# Sensor_PCB_M3.net
KiCad netlist of a schematic drawn in EAGLE
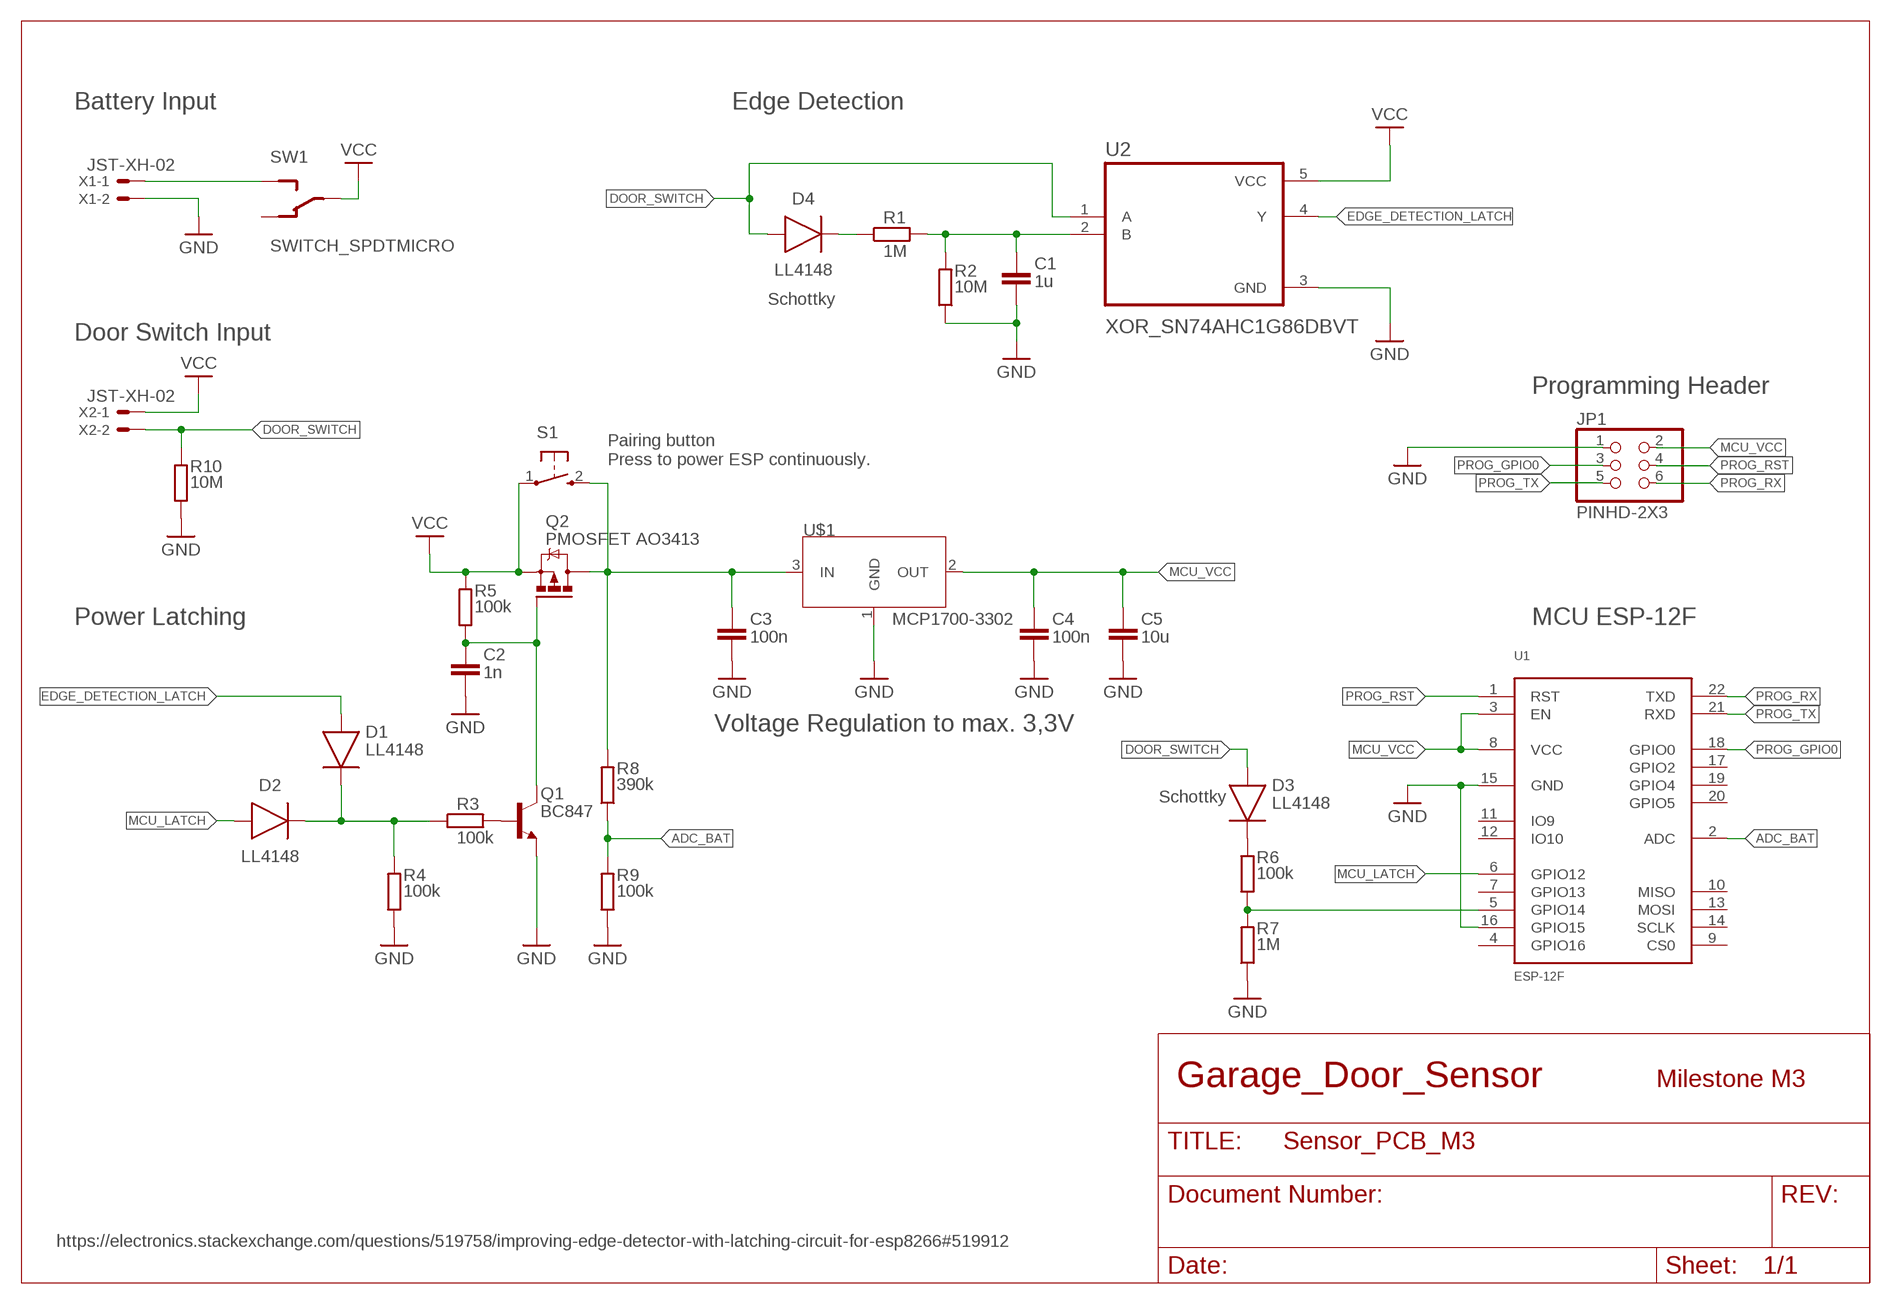
[diagram p0: schematic, sheet 1]

(export (version "E")
  (design (tool "Eeschema 10.0.6"))
  (components
    (comp (ref "C1")
      (value "1u")
      (footprint "eagle-import:CAPC2012X110")
      (libsource (lib "eagle-import") (part "CCHIP-0805(2012-METRIC)_"))
    )
    (comp (ref "C2")
      (value "1n")
      (footprint "eagle-import:CAPC2012X110")
      (libsource (lib "eagle-import") (part "CCHIP-0805(2012-METRIC)_"))
    )
    (comp (ref "C3")
      (value "100n")
      (footprint "eagle-import:CAPC2012X110")
      (libsource (lib "eagle-import") (part "CCHIP-0805(2012-METRIC)_"))
    )
    (comp (ref "C4")
      (value "100n")
      (footprint "eagle-import:CAPC2012X110")
      (libsource (lib "eagle-import") (part "CCHIP-0805(2012-METRIC)_"))
    )
    (comp (ref "C5")
      (value "10u")
      (footprint "eagle-import:CAPC2012X110")
      (libsource (lib "eagle-import") (part "CCHIP-0805(2012-METRIC)_"))
    )
    (comp (ref "D1")
      (value "LL4148")
      (footprint "eagle-import:DIOMELF3516")
      (fields (field (name "MANUFACTURER") "ON Semiconductor "))
      (libsource (lib "eagle-import") (part "DIODE__SOD-80LL4148"))
    )
    (comp (ref "D2")
      (value "LL4148")
      (footprint "eagle-import:DIOMELF3516")
      (fields (field (name "MANUFACTURER") "ON Semiconductor "))
      (libsource (lib "eagle-import") (part "DIODE__SOD-80LL4148"))
    )
    (comp (ref "D3")
      (value "LL4148")
      (footprint "eagle-import:DIOMELF3516")
      (fields (field (name "MANUFACTURER") "ON Semiconductor "))
      (libsource (lib "eagle-import") (part "DIODE__SOD-80LL4148"))
    )
    (comp (ref "D4")
      (value "LL4148")
      (footprint "eagle-import:DIOMELF3516")
      (fields (field (name "MANUFACTURER") "ON Semiconductor "))
      (libsource (lib "eagle-import") (part "DIODE__SOD-80LL4148"))
    )
    (comp (ref "JP1")
      (value "PINHD-2X3")
      (footprint "eagle-import:2X03")
      (fields (field (name "MANUFACTURER") "Generic"))
      (libsource (lib "eagle-import") (part "PINHD-2X3"))
    )
    (comp (ref "Q1")
      (value "BC847")
      (footprint "eagle-import:SOT95P237X112-3N")
      (libsource (lib "eagle-import") (part "NPNSOT23-BEC_"))
    )
    (comp (ref "Q2")
      (value "PMOSFET AO3413")
      (footprint "eagle-import:SOT23")
      (libsource (lib "eagle-import") (part "PMOSFETSOT23-GSD_"))
    )
    (comp (ref "R1")
      (value "1M")
      (footprint "eagle-import:R0805")
      (libsource (lib "eagle-import") (part "R-EU_R0805"))
    )
    (comp (ref "R2")
      (value "10M")
      (footprint "eagle-import:R0805")
      (libsource (lib "eagle-import") (part "R-EU_R0805"))
    )
    (comp (ref "R3")
      (value "100k")
      (footprint "eagle-import:R0805")
      (libsource (lib "eagle-import") (part "R-EU_R0805"))
    )
    (comp (ref "R4")
      (value "100k")
      (footprint "eagle-import:R0805")
      (libsource (lib "eagle-import") (part "R-EU_R0805"))
    )
    (comp (ref "R5")
      (value "100k")
      (footprint "eagle-import:R0805")
      (libsource (lib "eagle-import") (part "R-EU_R0805"))
    )
    (comp (ref "R6")
      (value "100k")
      (footprint "eagle-import:R0805")
      (libsource (lib "eagle-import") (part "R-EU_R0805"))
    )
    (comp (ref "R7")
      (value "1M")
      (footprint "eagle-import:R0805")
      (libsource (lib "eagle-import") (part "R-EU_R0805"))
    )
    (comp (ref "R8")
      (value "390k")
      (footprint "eagle-import:R0805")
      (libsource (lib "eagle-import") (part "R-EU_R0805"))
    )
    (comp (ref "R9")
      (value "100k")
      (footprint "eagle-import:R0805")
      (libsource (lib "eagle-import") (part "R-EU_R0805"))
    )
    (comp (ref "R10")
      (value "10M")
      (footprint "eagle-import:R0805")
      (libsource (lib "eagle-import") (part "R-EU_R0805"))
    )
    (comp (ref "S1")
      (value "KURZHUBTASTER")
      (footprint "eagle-import:B3F-10XX")
      (libsource (lib "eagle-import") (part "KURZHUBTASTER"))
    )
    (comp (ref "SW1")
      (value "SWITCH_SPDTMICRO")
      (footprint "eagle-import:MICROSWITCH_SPDT")
      (libsource (lib "eagle-import") (part "SWITCH_SPDTMICRO"))
    )
    (comp (ref "U$1")
      (value "MCP1700-3302")
      (footprint "eagle-import:SOT23")
      (libsource (lib "eagle-import") (part "MCP1700-3302"))
    )
    (comp (ref "U1")
      (value "ESP-12F")
      (footprint "eagle-import:ESP-12F")
      (fields (field (name "MF") "AI-Thinker"))
      (libsource (lib "eagle-import") (part "ESP-12F"))
    )
    (comp (ref "U2")
      (value "XOR_SN74AHC1G86DBVT")
      (footprint "eagle-import:SOT95P280X145-5N")
      (fields (field (name "MF") "Texas Instruments") (field (name "MP") "SN74AHC1G86DBVT"))
      (libsource (lib "eagle-import") (part "SN74AHC1G86DBVT"))
    )
    (comp (ref "X1")
      (value "JST-XH-02")
      (footprint "eagle-import:JST-XH-02-PACKAGE-LONG-PAD")
      (libsource (lib "eagle-import") (part "JST-XH-02-PIN-LONG-PAD"))
    )
    (comp (ref "X2")
      (value "JST-XH-02")
      (footprint "eagle-import:JST-XH-02-PACKAGE-LONG-PAD")
      (libsource (lib "eagle-import") (part "JST-XH-02-PIN-LONG-PAD"))
    )
  )
  (nets
    (net (code "1") (name "ADC_BAT") (class "Default")
      (node (ref "R8") (pin "1") (pinfunction "1_1") (pintype "passive"))
      (node (ref "R9") (pin "2") (pinfunction "2_2") (pintype "passive"))
      (node (ref "U1") (pin "2") (pinfunction "ADC_2") (pintype "bidirectional"))
    )
    (net (code "2") (name "DOOR_SWITCH") (class "Default")
      (node (ref "D3") (pin "2") (pinfunction "A_2") (pintype "passive"))
      (node (ref "D4") (pin "2") (pinfunction "A_2") (pintype "passive"))
      (node (ref "R10") (pin "2") (pinfunction "2_2") (pintype "passive"))
      (node (ref "U2") (pin "1") (pinfunction "A_1") (pintype "input"))
      (node (ref "X2") (pin "2") (pinfunction "S_2") (pintype "passive"))
    )
    (net (code "3") (name "EDGE_DETECTION_LATCH") (class "Default")
      (node (ref "D1") (pin "2") (pinfunction "A_2") (pintype "passive"))
      (node (ref "U2") (pin "4") (pinfunction "Y_4") (pintype "output"))
    )
    (net (code "4") (name "GND") (class "Default")
      (node (ref "C1") (pin "2") (pinfunction "2_2") (pintype "passive"))
      (node (ref "C2") (pin "2") (pinfunction "2_2") (pintype "passive"))
      (node (ref "C3") (pin "2") (pinfunction "2_2") (pintype "passive"))
      (node (ref "C4") (pin "2") (pinfunction "2_2") (pintype "passive"))
      (node (ref "C5") (pin "2") (pinfunction "2_2") (pintype "passive"))
      (node (ref "JP1") (pin "1") (pinfunction "1_1") (pintype "passive"))
      (node (ref "Q1") (pin "2") (pinfunction "E_2") (pintype "passive"))
      (node (ref "R10") (pin "1") (pinfunction "1_1") (pintype "passive"))
      (node (ref "R2") (pin "1") (pinfunction "1_1") (pintype "passive"))
      (node (ref "R4") (pin "1") (pinfunction "1_1") (pintype "passive"))
      (node (ref "R7") (pin "1") (pinfunction "1_1") (pintype "passive"))
      (node (ref "R9") (pin "1") (pinfunction "1_1") (pintype "passive"))
      (node (ref "U$1") (pin "1") (pinfunction "GND_1") (pintype "bidirectional"))
      (node (ref "U1") (pin "15") (pinfunction "GND_15") (pintype "bidirectional"))
      (node (ref "U1") (pin "16") (pinfunction "GPIO15_16") (pintype "bidirectional"))
      (node (ref "U2") (pin "3") (pinfunction "GND_3") (pintype "power_in"))
      (node (ref "X1") (pin "2") (pinfunction "S_2") (pintype "passive"))
    )
    (net (code "5") (name "MCU_LATCH") (class "Default")
      (node (ref "D2") (pin "2") (pinfunction "A_2") (pintype "passive"))
      (node (ref "U1") (pin "6") (pinfunction "GPIO12_6") (pintype "bidirectional"))
    )
    (net (code "6") (name "MCU_VCC") (class "Default")
      (node (ref "C4") (pin "1") (pinfunction "1_1") (pintype "passive"))
      (node (ref "C5") (pin "1") (pinfunction "1_1") (pintype "passive"))
      (node (ref "JP1") (pin "2") (pinfunction "2_2") (pintype "passive"))
      (node (ref "U$1") (pin "2") (pinfunction "OUT_2") (pintype "bidirectional"))
      (node (ref "U1") (pin "3") (pinfunction "EN_3") (pintype "bidirectional"))
      (node (ref "U1") (pin "8") (pinfunction "VCC_8") (pintype "bidirectional"))
    )
    (net (code "7") (name "Net-(D1-C)") (class "Default")
      (node (ref "D1") (pin "1") (pinfunction "C_1") (pintype "passive"))
      (node (ref "D2") (pin "1") (pinfunction "C_1") (pintype "passive"))
      (node (ref "R3") (pin "1") (pinfunction "1_1") (pintype "passive"))
      (node (ref "R4") (pin "2") (pinfunction "2_2") (pintype "passive"))
    )
    (net (code "8") (name "Net-(D3-C)") (class "Default")
      (node (ref "D3") (pin "1") (pinfunction "C_1") (pintype "passive"))
      (node (ref "R6") (pin "2") (pinfunction "2_2") (pintype "passive"))
    )
    (net (code "9") (name "Net-(D4-C)") (class "Default")
      (node (ref "D4") (pin "1") (pinfunction "C_1") (pintype "passive"))
      (node (ref "R1") (pin "1") (pinfunction "1_1") (pintype "passive"))
    )
    (net (code "10") (name "Net-(Q1-B)") (class "Default")
      (node (ref "Q1") (pin "1") (pinfunction "B_1") (pintype "passive"))
      (node (ref "R3") (pin "2") (pinfunction "2_2") (pintype "passive"))
    )
    (net (code "11") (name "Net-(Q1-C)") (class "Default")
      (node (ref "C2") (pin "1") (pinfunction "1_1") (pintype "passive"))
      (node (ref "Q1") (pin "3") (pinfunction "C_3") (pintype "passive"))
      (node (ref "Q2") (pin "1") (pinfunction "G_1") (pintype "passive"))
      (node (ref "R5") (pin "1") (pinfunction "1_1") (pintype "passive"))
    )
    (net (code "12") (name "Net-(Q2-D)") (class "Default")
      (node (ref "C3") (pin "1") (pinfunction "1_1") (pintype "passive"))
      (node (ref "Q2") (pin "3") (pinfunction "D_3") (pintype "passive"))
      (node (ref "R8") (pin "2") (pinfunction "2_2") (pintype "passive"))
      (node (ref "S1") (pin "2") (pinfunction "S_2") (pintype "passive"))
      (node (ref "U$1") (pin "3") (pinfunction "IN_3") (pintype "bidirectional"))
    )
    (net (code "13") (name "Net-(U1-GPIO14)") (class "Default")
      (node (ref "R6") (pin "1") (pinfunction "1_1") (pintype "passive"))
      (node (ref "R7") (pin "2") (pinfunction "2_2") (pintype "passive"))
      (node (ref "U1") (pin "5") (pinfunction "GPIO14_5") (pintype "bidirectional"))
    )
    (net (code "14") (name "Net-(U2-B)") (class "Default")
      (node (ref "C1") (pin "1") (pinfunction "1_1") (pintype "passive"))
      (node (ref "R1") (pin "2") (pinfunction "2_2") (pintype "passive"))
      (node (ref "R2") (pin "2") (pinfunction "2_2") (pintype "passive"))
      (node (ref "U2") (pin "2") (pinfunction "B_2") (pintype "input"))
    )
    (net (code "15") (name "Net-(X1A-S)") (class "Default")
      (node (ref "SW1") (pin "P$1") (pinfunction "P$1_P$1") (pintype "passive"))
      (node (ref "X1") (pin "1") (pinfunction "S_1") (pintype "passive"))
    )
    (net (code "16") (name "PROG_GPIO0") (class "Default")
      (node (ref "JP1") (pin "3") (pinfunction "3_3") (pintype "passive"))
      (node (ref "U1") (pin "18") (pinfunction "GPIO0_18") (pintype "bidirectional"))
    )
    (net (code "17") (name "PROG_RST") (class "Default")
      (node (ref "JP1") (pin "4") (pinfunction "4_4") (pintype "passive"))
      (node (ref "U1") (pin "1") (pinfunction "RST_1") (pintype "bidirectional"))
    )
    (net (code "18") (name "PROG_RX") (class "Default")
      (node (ref "JP1") (pin "6") (pinfunction "6_6") (pintype "passive"))
      (node (ref "U1") (pin "22") (pinfunction "TXD_22") (pintype "bidirectional"))
    )
    (net (code "19") (name "PROG_TX") (class "Default")
      (node (ref "JP1") (pin "5") (pinfunction "5_5") (pintype "passive"))
      (node (ref "U1") (pin "21") (pinfunction "RXD_21") (pintype "bidirectional"))
    )
    (net (code "20") (name "VCC") (class "Default")
      (node (ref "Q2") (pin "2") (pinfunction "S_2") (pintype "passive"))
      (node (ref "R5") (pin "2") (pinfunction "2_2") (pintype "passive"))
      (node (ref "S1") (pin "1") (pinfunction "P_1") (pintype "passive"))
      (node (ref "SW1") (pin "P$2") (pinfunction "P$2_P$2") (pintype "passive"))
      (node (ref "U2") (pin "5") (pinfunction "VCC_5") (pintype "power_in"))
      (node (ref "X2") (pin "1") (pinfunction "S_1") (pintype "passive"))
    )
    (net (code "21") (name "unconnected-(SW1-PadP$3)") (class "Default")
      (node (ref "SW1") (pin "P$3") (pinfunction "P$3_P$3") (pintype "passive"))
    )
    (net (code "22") (name "unconnected-(U1-CS0-Pad9)") (class "Default")
      (node (ref "U1") (pin "9") (pinfunction "CS0_9") (pintype "bidirectional"))
    )
    (net (code "23") (name "unconnected-(U1-GPIO2-Pad17)") (class "Default")
      (node (ref "U1") (pin "17") (pinfunction "GPIO2_17") (pintype "bidirectional"))
    )
    (net (code "24") (name "unconnected-(U1-GPIO4-Pad19)") (class "Default")
      (node (ref "U1") (pin "19") (pinfunction "GPIO4_19") (pintype "bidirectional"))
    )
    (net (code "25") (name "unconnected-(U1-GPIO5-Pad20)") (class "Default")
      (node (ref "U1") (pin "20") (pinfunction "GPIO5_20") (pintype "bidirectional"))
    )
    (net (code "26") (name "unconnected-(U1-GPIO13-Pad7)") (class "Default")
      (node (ref "U1") (pin "7") (pinfunction "GPIO13_7") (pintype "bidirectional"))
    )
    (net (code "27") (name "unconnected-(U1-GPIO16-Pad4)") (class "Default")
      (node (ref "U1") (pin "4") (pinfunction "GPIO16_4") (pintype "bidirectional"))
    )
    (net (code "28") (name "unconnected-(U1-IO9-Pad11)") (class "Default")
      (node (ref "U1") (pin "11") (pinfunction "IO9_11") (pintype "bidirectional"))
    )
    (net (code "29") (name "unconnected-(U1-IO10-Pad12)") (class "Default")
      (node (ref "U1") (pin "12") (pinfunction "IO10_12") (pintype "bidirectional"))
    )
    (net (code "30") (name "unconnected-(U1-MISO-Pad10)") (class "Default")
      (node (ref "U1") (pin "10") (pinfunction "MISO_10") (pintype "bidirectional"))
    )
    (net (code "31") (name "unconnected-(U1-MOSI-Pad13)") (class "Default")
      (node (ref "U1") (pin "13") (pinfunction "MOSI_13") (pintype "bidirectional"))
    )
    (net (code "32") (name "unconnected-(U1-SCLK-Pad14)") (class "Default")
      (node (ref "U1") (pin "14") (pinfunction "SCLK_14") (pintype "bidirectional"))
    )
  )
)
